# powertrain.net
KiCad netlist of a schematic drawn in Altium Designer
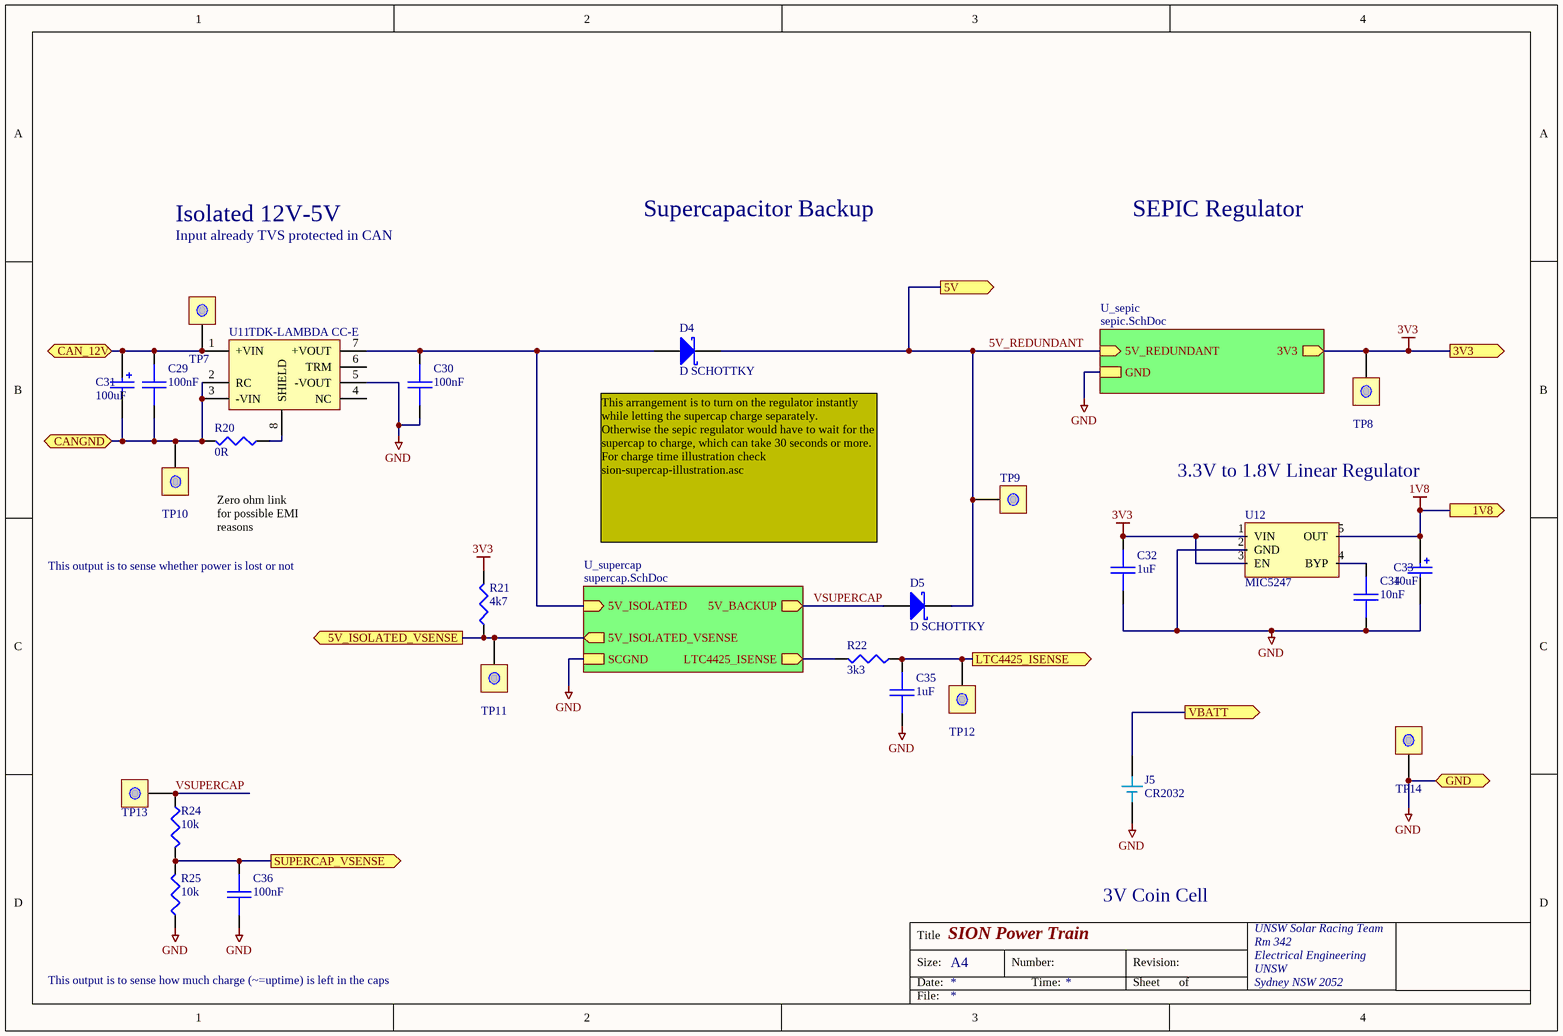
[diagram p0: powertrain.SchDoc]

(export (version "E")
  (design (tool "Eeschema 10.0.6"))
  (components
    (comp (ref "C29")
      (value "100nF")
      (footprint "0603")
      (description "Capacitor")
      (libsource (lib "RCLDQ") (part "CAP"))
    )
    (comp (ref "C30")
      (value "100nF")
      (footprint "0603")
      (description "Capacitor")
      (libsource (lib "RCLDQ") (part "CAP"))
    )
    (comp (ref "C31")
      (value "100uF")
      (footprint "MCCT-CASED")
      (description "Polarized Capacitor (Surface Mount)")
      (libsource (lib "RCLDQ") (part "CAP POL3"))
    )
    (comp (ref "C32")
      (value "1uF")
      (footprint "0805")
      (description "Capacitor")
      (libsource (lib "RCLDQ") (part "CAP"))
    )
    (comp (ref "C33")
      (value "10uF")
      (footprint "MCCT-CASEA")
      (description "Polarized Capacitor (Surface Mount)")
      (libsource (lib "RCLDQ") (part "CAP POL3"))
    )
    (comp (ref "C34")
      (value "10nF")
      (footprint "0603")
      (description "Capacitor")
      (libsource (lib "RCLDQ") (part "CAP"))
    )
    (comp (ref "C35")
      (value "1uF")
      (footprint "0805")
      (description "Capacitor")
      (libsource (lib "RCLDQ") (part "CAP"))
    )
    (comp (ref "C36")
      (value "100nF")
      (footprint "0603")
      (description "Capacitor")
      (libsource (lib "RCLDQ") (part "CAP"))
    )
    (comp (ref "D4")
      (value "D SCHOTTKY")
      (footprint "DIODE-D1.5mm")
      (description "Schottky Diode")
      (libsource (lib "RCLDQ") (part "D SCHOTTKY"))
    )
    (comp (ref "D5")
      (value "D SCHOTTKY")
      (footprint "DIODE-D1.5mm")
      (description "Schottky Diode")
      (libsource (lib "RCLDQ") (part "D SCHOTTKY"))
    )
    (comp (ref "J5")
      (value "CR2032")
      (footprint "CR2032_VERTICAL")
      (description "Battery Coin CR2032 3V")
      (libsource (lib "sion") (part "CR2032"))
    )
    (comp (ref "R20")
      (value "0R")
      (footprint "1206")
      (description "Resistor")
      (libsource (lib "RCLDQ") (part "RES1"))
    )
    (comp (ref "R21")
      (value "4k7")
      (footprint "0603")
      (description "Resistor")
      (libsource (lib "RCLDQ") (part "RES1"))
    )
    (comp (ref "R22")
      (value "3k3")
      (footprint "0603")
      (description "Resistor")
      (libsource (lib "RCLDQ") (part "RES1"))
    )
    (comp (ref "R24")
      (value "10k")
      (footprint "0805")
      (description "Resistor")
      (libsource (lib "RCLDQ") (part "RES1"))
    )
    (comp (ref "R25")
      (value "10k")
      (footprint "0805")
      (description "Resistor")
      (libsource (lib "RCLDQ") (part "RES1"))
    )
    (comp (ref "TP7")
      (value "CAN12V")
      (footprint "TESTPOINT")
      (description "TEST POINT")
      (libsource (lib "") (part "TEST_1"))
    )
    (comp (ref "TP8")
      (value "3V3")
      (footprint "TESTPOINT")
      (description "TEST POINT")
      (libsource (lib "Miscellaneous") (part "TEST"))
    )
    (comp (ref "TP9")
      (value "5V")
      (footprint "TESTPOINT")
      (description "TEST POINT")
      (libsource (lib "") (part "TEST_2"))
    )
    (comp (ref "TP10")
      (value "CANGND")
      (footprint "TESTPOINT")
      (description "TEST POINT")
      (libsource (lib "Miscellaneous") (part "TEST"))
    )
    (comp (ref "TP11")
      (value "VSENSE")
      (footprint "TESTPOINT")
      (description "TEST POINT")
      (libsource (lib "Miscellaneous") (part "TEST"))
    )
    (comp (ref "TP12")
      (value "ISENSE")
      (footprint "TESTPOINT")
      (description "TEST POINT")
      (libsource (lib "Miscellaneous") (part "TEST"))
    )
    (comp (ref "TP13")
      (value "VCAP")
      (footprint "TESTPOINT")
      (description "TEST POINT")
      (libsource (lib "") (part "TEST_3"))
    )
    (comp (ref "TP14")
      (value "GND")
      (footprint "TESTPOINT")
      (description "TEST POINT")
      (libsource (lib "") (part "TEST_1"))
    )
    (comp (ref "U11")
      (value "TDK-LAMBDA CC-E")
      (footprint "CC10-F-E")
      (description "Isolated DC-DC Converter")
      (libsource (lib "sion") (part "CC10-F-E"))
    )
    (comp (ref "U12")
      (value "MIC5247")
      (footprint "SOT23-5")
      (description "150mA Low-Voltage Linear Regulator")
      (libsource (lib "gumstix") (part "MIC5247"))
    )
  )
  (nets
    (net (code "1") (name "/5V_ISOLATED") (class "Default")
      (node (ref "C30") (pin "1") (pinfunction "1_1") (pintype "passive"))
      (node (ref "D4") (pin "A") (pinfunction "A_A") (pintype "passive"))
      (node (ref "U11") (pin "7") (pinfunction "+VOUT_7") (pintype "passive"))
    )
    (net (code "2") (name "/5V_ISOLATED_VSENSE") (class "Default")
      (node (ref "R21") (pin "1") (pinfunction "1_1") (pintype "passive"))
      (node (ref "TP11") (pin "0") (pinfunction "TP_0") (pintype "passive"))
    )
    (net (code "3") (name "/5V_REDUNDANT") (class "Default")
      (node (ref "D4") (pin "K") (pinfunction "K_K") (pintype "passive"))
      (node (ref "D5") (pin "K") (pinfunction "K_K") (pintype "passive"))
      (node (ref "TP9") (pin "0") (pinfunction "TP_0") (pintype "passive"))
    )
    (net (code "4") (name "/CANGND") (class "Default")
      (node (ref "C29") (pin "2") (pinfunction "2_2") (pintype "passive"))
      (node (ref "C31") (pin "2") (pinfunction "2_2") (pintype "passive"))
      (node (ref "R20") (pin "2") (pinfunction "2_2") (pintype "passive"))
      (node (ref "TP10") (pin "0") (pinfunction "TP_0") (pintype "passive"))
      (node (ref "U11") (pin "2") (pinfunction "RC_2") (pintype "passive"))
      (node (ref "U11") (pin "3") (pinfunction "-VIN_3") (pintype "passive"))
    )
    (net (code "5") (name "/CAN_12V") (class "Default")
      (node (ref "C29") (pin "1") (pinfunction "1_1") (pintype "passive"))
      (node (ref "C31") (pin "1") (pinfunction "1_1") (pintype "passive"))
      (node (ref "TP7") (pin "0") (pinfunction "TP_0") (pintype "passive"))
      (node (ref "U11") (pin "1") (pinfunction "+VIN_1") (pintype "passive"))
    )
    (net (code "6") (name "/LTC4425_ISENSE") (class "Default")
      (node (ref "C35") (pin "1") (pinfunction "1_1") (pintype "passive"))
      (node (ref "R22") (pin "1") (pinfunction "1_1") (pintype "passive"))
      (node (ref "TP12") (pin "0") (pinfunction "TP_0") (pintype "passive"))
    )
    (net (code "7") (name "/LTC4425_ISENSE_1") (class "Default")
      (node (ref "R22") (pin "2") (pinfunction "2_2") (pintype "passive"))
    )
    (net (code "8") (name "/SUPERCAP_VSENSE") (class "Default")
      (node (ref "C36") (pin "1") (pinfunction "1_1") (pintype "passive"))
      (node (ref "R24") (pin "2") (pinfunction "2_2") (pintype "passive"))
      (node (ref "R25") (pin "2") (pinfunction "2_2") (pintype "passive"))
    )
    (net (code "9") (name "/VBATT") (class "Default")
      (node (ref "J5") (pin "1") (pinfunction "3V_1") (pintype "passive"))
    )
    (net (code "10") (name "/VSUPERCAP") (class "Default")
      (node (ref "D5") (pin "A") (pinfunction "A_A") (pintype "passive"))
      (node (ref "R24") (pin "1") (pinfunction "1_1") (pintype "passive"))
      (node (ref "TP13") (pin "0") (pinfunction "TP_0") (pintype "passive"))
    )
    (net (code "11") (name "1V8") (class "Default")
      (node (ref "C33") (pin "1") (pinfunction "1_1") (pintype "passive"))
      (node (ref "U12") (pin "5") (pinfunction "OUT_5") (pintype "passive"))
    )
    (net (code "12") (name "3V3") (class "Default")
      (node (ref "C32") (pin "1") (pinfunction "1_1") (pintype "passive"))
      (node (ref "R21") (pin "2") (pinfunction "2_2") (pintype "passive"))
      (node (ref "TP8") (pin "0") (pinfunction "TP_0") (pintype "passive"))
      (node (ref "U12") (pin "1") (pinfunction "VIN_1") (pintype "passive"))
      (node (ref "U12") (pin "3") (pinfunction "EN_3") (pintype "passive"))
    )
    (net (code "13") (name "GND") (class "Default")
      (node (ref "C30") (pin "2") (pinfunction "2_2") (pintype "passive"))
      (node (ref "C32") (pin "2") (pinfunction "2_2") (pintype "passive"))
      (node (ref "C33") (pin "2") (pinfunction "2_2") (pintype "passive"))
      (node (ref "C34") (pin "2") (pinfunction "2_2") (pintype "passive"))
      (node (ref "C35") (pin "2") (pinfunction "2_2") (pintype "passive"))
      (node (ref "C36") (pin "2") (pinfunction "2_2") (pintype "passive"))
      (node (ref "J5") (pin "2") (pintype "passive"))
      (node (ref "R25") (pin "1") (pinfunction "1_1") (pintype "passive"))
      (node (ref "TP14") (pin "0") (pinfunction "TP_0") (pintype "passive"))
      (node (ref "U11") (pin "5") (pinfunction "-VOUT_5") (pintype "passive"))
      (node (ref "U12") (pin "2") (pinfunction "GND_2") (pintype "passive"))
    )
    (net (code "14") (name "Net-(U11-SHIELD)") (class "Default")
      (node (ref "R20") (pin "1") (pinfunction "1_1") (pintype "passive"))
      (node (ref "U11") (pin "8") (pinfunction "SHIELD_8") (pintype "passive"))
    )
    (net (code "15") (name "Net-(U12-BYP)") (class "Default")
      (node (ref "C34") (pin "1") (pinfunction "1_1") (pintype "passive"))
      (node (ref "U12") (pin "4") (pinfunction "BYP_4") (pintype "passive"))
    )
    (net (code "16") (name "unconnected-(U11-NC-Pad4)") (class "Default")
      (node (ref "U11") (pin "4") (pinfunction "NC_4") (pintype "passive"))
    )
    (net (code "17") (name "unconnected-(U11-TRM-Pad6)") (class "Default")
      (node (ref "U11") (pin "6") (pinfunction "TRM_6") (pintype "passive"))
    )
  )
)
